# design.net
KiCad netlist of a schematic drawn in Altium Designer
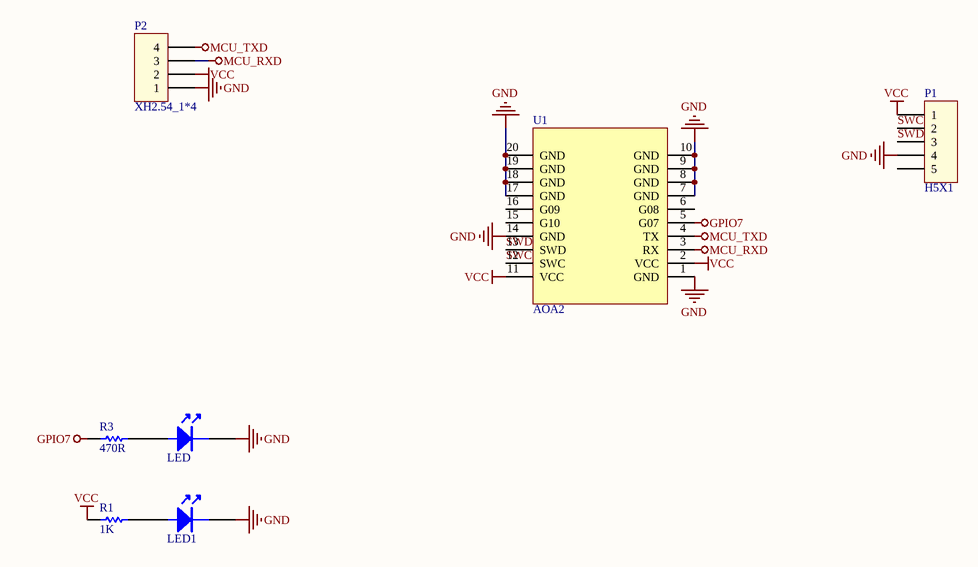
[diagram p0: 基站转接板原理图.SchDoc]

(export (version "E")
  (design (tool "Eeschema 10.0.6"))
  (components
    (comp (ref "LED") (value "LED") (footprint "LED_0603") (libsource (lib "MIAO") (part "ALX_LED")))
    (comp (ref "LED1") (value "LED") (footprint "LED_0603") (libsource (lib "MIAO") (part "ALX_LED")))
    (comp (ref "P1") (value "H5X1") (footprint "H1.27-1X5") (libsource (lib "MIAO") (part "H5X1")))
    (comp (ref "P2")
      (value "XH2.54_1*4")
      (footprint "XH2.54-LI-4P")
      (libsource (lib "MIAO") (part "XH2.54_1*4"))
    )
    (comp (ref "R1") (value "1K") (footprint "ALX_0603A") (libsource (lib "MIAO") (part "ALX_RES")))
    (comp (ref "R3") (value "470R") (footprint "ALX_0603A") (libsource (lib "MIAO") (part "ALX_RES")))
    (comp (ref "U1") (value "AOA2") (footprint "4ANTA") (libsource (lib "MIAO") (part "AOA2")))
  )
  (nets
    (net (code "1") (name "/SWC") (class "Default")
      (node (ref "P1") (pin "2") (pinfunction "2_2") (pintype "passive"))
      (node (ref "U1") (pin "12") (pinfunction "SWC_12") (pintype "passive"))
    )
    (net (code "2") (name "/SWD") (class "Default")
      (node (ref "P1") (pin "3") (pinfunction "3_3") (pintype "passive"))
      (node (ref "U1") (pin "13") (pinfunction "SWD_13") (pintype "passive"))
    )
    (net (code "3") (name "GND") (class "Default")
      (node (ref "LED") (pin "2") (pinfunction "2_2") (pintype "passive"))
      (node (ref "LED1") (pin "2") (pinfunction "2_2") (pintype "passive"))
      (node (ref "P1") (pin "4") (pinfunction "4_4") (pintype "passive"))
      (node (ref "P2") (pin "1") (pinfunction "1_1") (pintype "passive"))
      (node (ref "U1") (pin "1") (pinfunction "GND_1") (pintype "passive"))
      (node (ref "U1") (pin "10") (pinfunction "GND_10") (pintype "passive"))
      (node (ref "U1") (pin "14") (pinfunction "GND_14") (pintype "passive"))
      (node (ref "U1") (pin "17") (pinfunction "GND_17") (pintype "passive"))
      (node (ref "U1") (pin "18") (pinfunction "GND_18") (pintype "passive"))
      (node (ref "U1") (pin "19") (pinfunction "GND_19") (pintype "passive"))
      (node (ref "U1") (pin "20") (pinfunction "GND_20") (pintype "passive"))
      (node (ref "U1") (pin "7") (pinfunction "GND_7") (pintype "passive"))
      (node (ref "U1") (pin "8") (pinfunction "GND_8") (pintype "passive"))
      (node (ref "U1") (pin "9") (pinfunction "GND_9") (pintype "passive"))
    )
    (net (code "4") (name "GPIO7") (class "Default")
      (node (ref "R3") (pin "1") (pinfunction "1_1") (pintype "passive"))
      (node (ref "U1") (pin "5") (pinfunction "G07_5") (pintype "passive"))
    )
    (net (code "5") (name "MCU_RXD") (class "Default")
      (node (ref "P2") (pin "3") (pinfunction "3_3") (pintype "passive"))
      (node (ref "U1") (pin "3") (pinfunction "RX_3") (pintype "passive"))
    )
    (net (code "6") (name "MCU_TXD") (class "Default")
      (node (ref "P2") (pin "4") (pinfunction "4_4") (pintype "passive"))
      (node (ref "U1") (pin "4") (pinfunction "TX_4") (pintype "passive"))
    )
    (net (code "7") (name "Net-(LED-Pad1)") (class "Default")
      (node (ref "LED") (pin "1") (pinfunction "1_1") (pintype "passive"))
      (node (ref "R3") (pin "2") (pinfunction "2_2") (pintype "passive"))
    )
    (net (code "8") (name "Net-(LED1-Pad1)") (class "Default")
      (node (ref "LED1") (pin "1") (pinfunction "1_1") (pintype "passive"))
      (node (ref "R1") (pin "2") (pinfunction "2_2") (pintype "passive"))
    )
    (net (code "9") (name "VCC") (class "Default")
      (node (ref "P1") (pin "1") (pinfunction "1_1") (pintype "passive"))
      (node (ref "P2") (pin "2") (pinfunction "2_2") (pintype "passive"))
      (node (ref "R1") (pin "1") (pinfunction "1_1") (pintype "passive"))
      (node (ref "U1") (pin "11") (pinfunction "VCC_11") (pintype "passive"))
      (node (ref "U1") (pin "2") (pinfunction "VCC_2") (pintype "passive"))
    )
    (net (code "10") (name "unconnected-(P1-Pad5)") (class "Default")
      (node (ref "P1") (pin "5") (pinfunction "5_5") (pintype "passive"))
    )
    (net (code "11") (name "unconnected-(U1-G08-Pad6)") (class "Default")
      (node (ref "U1") (pin "6") (pinfunction "G08_6") (pintype "passive"))
    )
    (net (code "12") (name "unconnected-(U1-G09-Pad16)") (class "Default")
      (node (ref "U1") (pin "16") (pinfunction "G09_16") (pintype "passive"))
    )
    (net (code "13") (name "unconnected-(U1-G10-Pad15)") (class "Default")
      (node (ref "U1") (pin "15") (pinfunction "G10_15") (pintype "passive"))
    )
  )
)
